# AdcUnit.net
KiCad netlist of a schematic drawn in Altium Designer
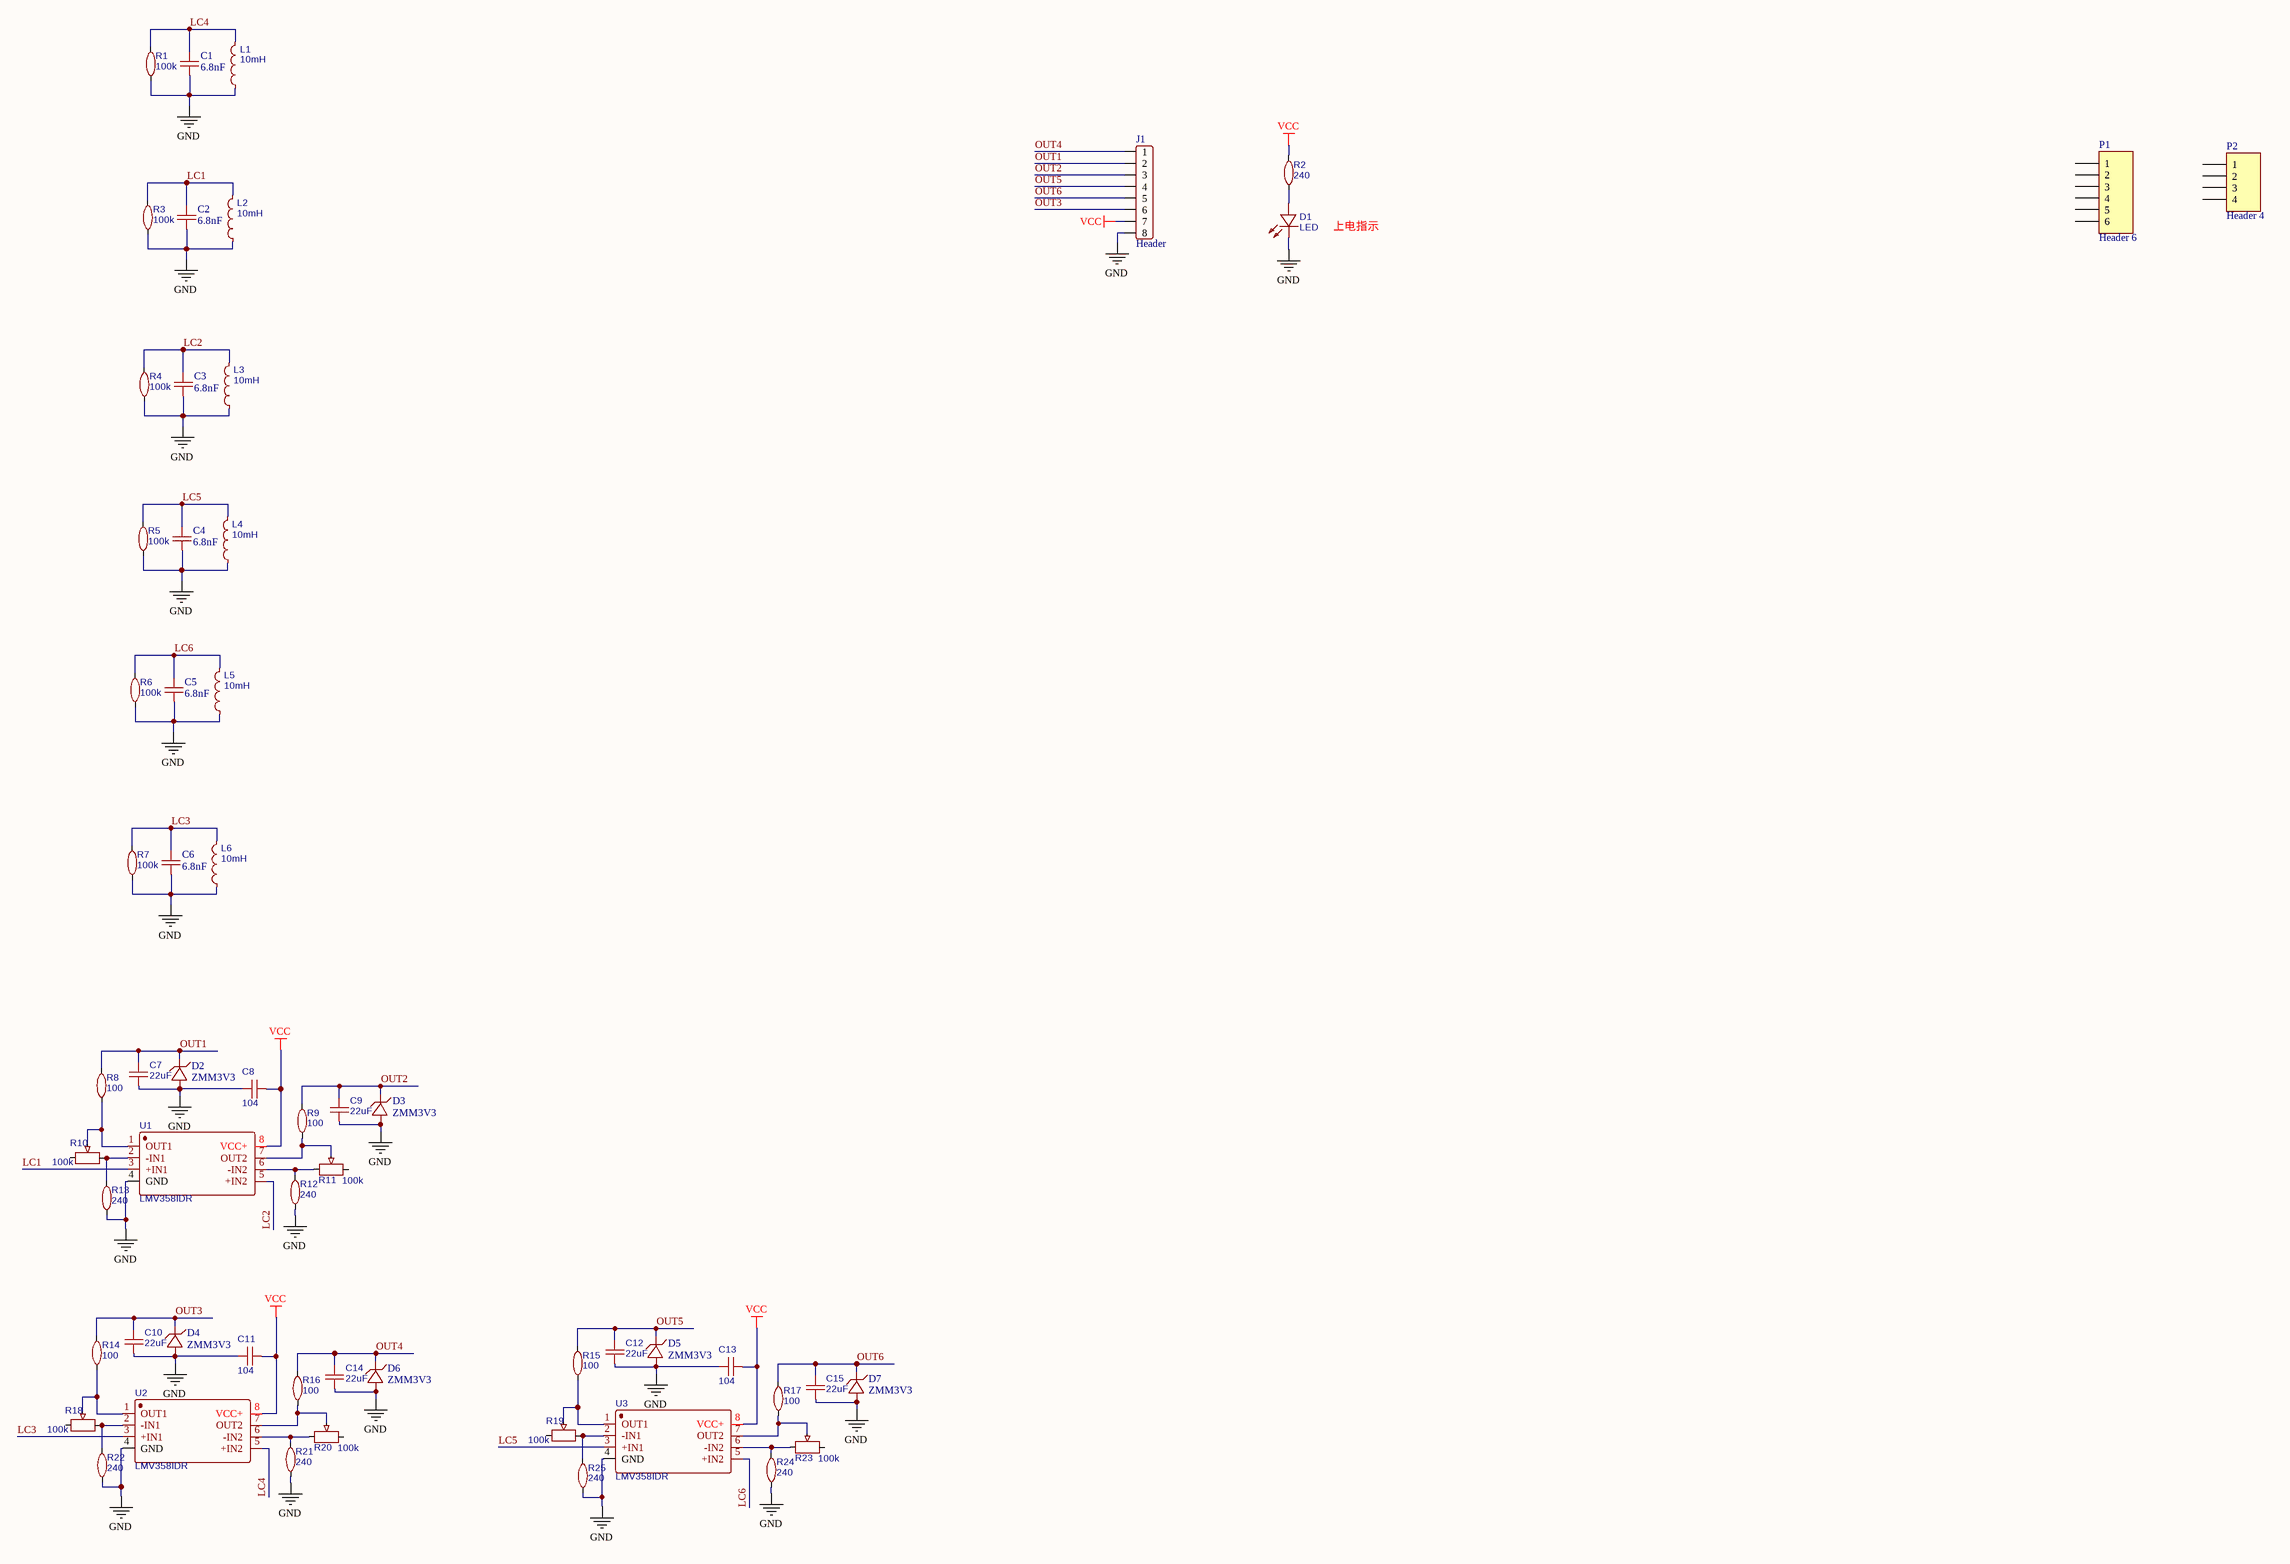
[diagram p0: AdcUnit.SchDoc]

(export (version "E")
  (design (tool "Eeschema 10.0.6"))
  (components
    (comp (ref "C1") (value "6.8nF") (footprint "CAP3") (libsource (lib "LTC_Library1") (part "CAP_聚苯电容")))
    (comp (ref "C2") (value "6.8nF") (footprint "CAP3") (libsource (lib "LTC_Library1") (part "CAP_聚苯电容")))
    (comp (ref "C3") (value "6.8nF") (footprint "CAP3") (libsource (lib "LTC_Library1") (part "CAP_聚苯电容")))
    (comp (ref "C4") (value "6.8nF") (footprint "CAP3") (libsource (lib "LTC_Library1") (part "CAP_聚苯电容")))
    (comp (ref "C5") (value "6.8nF") (footprint "CAP3") (libsource (lib "LTC_Library1") (part "CAP_聚苯电容")))
    (comp (ref "C6") (value "6.8nF") (footprint "CAP3") (libsource (lib "LTC_Library1") (part "CAP_聚苯电容")))
    (comp (ref "C7")
      (value "22uF")
      (footprint "CAP_0603")
      (fields
        (field (name "BOM_SUPPLIER PART") "C307348")
        (field (name "BOM_MANUFACTURER PART") "CL10B104KB8WPNC")
        (field (name "CONTRIBUTOR") "LCSC")
      )
      (libsource (lib "LTC_Library1") (part "CAP_0603"))
    )
    (comp (ref "C8")
      (value "104")
      (footprint "CAP_0603")
      (fields
        (field (name "BOM_SUPPLIER PART") "C307348")
        (field (name "BOM_MANUFACTURER PART") "CL10B104KB8WPNC")
        (field (name "CONTRIBUTOR") "LCSC")
      )
      (libsource (lib "LTC_Library1") (part "CAP_0603"))
    )
    (comp (ref "C9")
      (value "22uF")
      (footprint "CAP_0603")
      (fields
        (field (name "BOM_SUPPLIER PART") "C307348")
        (field (name "BOM_MANUFACTURER PART") "CL10B104KB8WPNC")
        (field (name "CONTRIBUTOR") "LCSC")
      )
      (libsource (lib "LTC_Library1") (part "CAP_0603"))
    )
    (comp (ref "C10")
      (value "22uF")
      (footprint "CAP_0603")
      (fields
        (field (name "BOM_SUPPLIER PART") "C307348")
        (field (name "BOM_MANUFACTURER PART") "CL10B104KB8WPNC")
        (field (name "CONTRIBUTOR") "LCSC")
      )
      (libsource (lib "LTC_Library1") (part "CAP_0603"))
    )
    (comp (ref "C11")
      (value "104")
      (footprint "CAP_0603")
      (fields
        (field (name "BOM_SUPPLIER PART") "C307348")
        (field (name "BOM_MANUFACTURER PART") "CL10B104KB8WPNC")
        (field (name "CONTRIBUTOR") "LCSC")
      )
      (libsource (lib "LTC_Library1") (part "CAP_0603"))
    )
    (comp (ref "C12")
      (value "22uF")
      (footprint "CAP_0603")
      (fields
        (field (name "BOM_SUPPLIER PART") "C307348")
        (field (name "BOM_MANUFACTURER PART") "CL10B104KB8WPNC")
        (field (name "CONTRIBUTOR") "LCSC")
      )
      (libsource (lib "LTC_Library1") (part "CAP_0603"))
    )
    (comp (ref "C13")
      (value "104")
      (footprint "CAP_0603")
      (fields
        (field (name "BOM_SUPPLIER PART") "C307348")
        (field (name "BOM_MANUFACTURER PART") "CL10B104KB8WPNC")
        (field (name "CONTRIBUTOR") "LCSC")
      )
      (libsource (lib "LTC_Library1") (part "CAP_0603"))
    )
    (comp (ref "C14")
      (value "22uF")
      (footprint "CAP_0603")
      (fields
        (field (name "BOM_SUPPLIER PART") "C307348")
        (field (name "BOM_MANUFACTURER PART") "CL10B104KB8WPNC")
        (field (name "CONTRIBUTOR") "LCSC")
      )
      (libsource (lib "LTC_Library1") (part "CAP_0603"))
    )
    (comp (ref "C15")
      (value "22uF")
      (footprint "CAP_0603")
      (fields
        (field (name "BOM_SUPPLIER PART") "C307348")
        (field (name "BOM_MANUFACTURER PART") "CL10B104KB8WPNC")
        (field (name "CONTRIBUTOR") "LCSC")
      )
      (libsource (lib "LTC_Library1") (part "CAP_0603"))
    )
    (comp (ref "D1")
      (value "LED")
      (footprint "LED_0603_B")
      (description "发光LED")
      (fields
        (field (name "BOM_MANUFACTURER PART") "D-G080508G1")
        (field (name "BOM_SUPPLIER PART") "C107402")
        (field (name "CONTRIBUTOR") "LCSC")
      )
      (libsource (lib "LTC_Library1") (part "LED_0603"))
    )
    (comp (ref "D2") (value "ZMM3V3") (footprint "LL34") (libsource (lib "LTC_Library1") (part "ZMM3V3")))
    (comp (ref "D3") (value "ZMM3V3") (footprint "LL34") (libsource (lib "LTC_Library1") (part "ZMM3V3")))
    (comp (ref "D4") (value "ZMM3V3") (footprint "LL34") (libsource (lib "LTC_Library1") (part "ZMM3V3")))
    (comp (ref "D5") (value "ZMM3V3") (footprint "LL34") (libsource (lib "LTC_Library1") (part "ZMM3V3")))
    (comp (ref "D6") (value "ZMM3V3") (footprint "LL34") (libsource (lib "LTC_Library1") (part "ZMM3V3")))
    (comp (ref "D7") (value "ZMM3V3") (footprint "LL34") (libsource (lib "LTC_Library1") (part "ZMM3V3")))
    (comp (ref "J1")
      (value "Header")
      (footprint "XH2.54-8P")
      (libsource (lib "LTC_Library1") (part "Header 2.54_8"))
    )
    (comp (ref "L1")
      (value "10mH")
      (footprint "Inductor_8x10")
      (fields
        (field (name "BOM_SUPPLIER PART") "C295130")
        (field (name "BOM_MANUFACTURER PART") "NLV25T-330J-EF")
        (field (name "CONTRIBUTOR") "LCSC")
      )
      (libsource (lib "LTC_Library1") (part "Inductor"))
    )
    (comp (ref "L2")
      (value "10mH")
      (footprint "Inductor_8x10")
      (fields
        (field (name "BOM_SUPPLIER PART") "C295130")
        (field (name "BOM_MANUFACTURER PART") "NLV25T-330J-EF")
        (field (name "CONTRIBUTOR") "LCSC")
      )
      (libsource (lib "LTC_Library1") (part "Inductor"))
    )
    (comp (ref "L3")
      (value "10mH")
      (footprint "Inductor_8x10")
      (fields
        (field (name "BOM_SUPPLIER PART") "C295130")
        (field (name "BOM_MANUFACTURER PART") "NLV25T-330J-EF")
        (field (name "CONTRIBUTOR") "LCSC")
      )
      (libsource (lib "LTC_Library1") (part "Inductor"))
    )
    (comp (ref "L4")
      (value "10mH")
      (footprint "Inductor_8x10")
      (fields
        (field (name "BOM_SUPPLIER PART") "C295130")
        (field (name "BOM_MANUFACTURER PART") "NLV25T-330J-EF")
        (field (name "CONTRIBUTOR") "LCSC")
      )
      (libsource (lib "LTC_Library1") (part "Inductor"))
    )
    (comp (ref "L5")
      (value "10mH")
      (footprint "Inductor_8x10")
      (fields
        (field (name "BOM_SUPPLIER PART") "C295130")
        (field (name "BOM_MANUFACTURER PART") "NLV25T-330J-EF")
        (field (name "CONTRIBUTOR") "LCSC")
      )
      (libsource (lib "LTC_Library1") (part "Inductor"))
    )
    (comp (ref "L6")
      (value "10mH")
      (footprint "Inductor_8x10")
      (fields
        (field (name "BOM_SUPPLIER PART") "C295130")
        (field (name "BOM_MANUFACTURER PART") "NLV25T-330J-EF")
        (field (name "CONTRIBUTOR") "LCSC")
      )
      (libsource (lib "LTC_Library1") (part "Inductor"))
    )
    (comp (ref "P1")
      (value "Header 6")
      (footprint "HDR-TH_6P_W")
      (description "Header, 6-Pin")
      (fields (field (name "PUBLISHER") "Altium Limited"))
      (libsource (lib "Miscellaneous Connectors") (part "Header 6"))
    )
    (comp (ref "P2")
      (value "Header 4")
      (footprint "XH2.54-4P")
      (description "Header, 4-Pin")
      (fields (field (name "PUBLISHER") "Altium Limited"))
      (libsource (lib "Miscellaneous Connectors") (part "Header 4"))
    )
    (comp (ref "R1")
      (value "100k")
      (footprint "RES_0603")
      (fields
        (field (name "BOM_MANUFACTURER PART") "RC0402JR-07100KL")
        (field (name "BOM_SUPPLIER PART") "C106234")
      )
      (libsource (lib "LTC_Library1") (part "RES_0603"))
    )
    (comp (ref "R2")
      (value "240")
      (footprint "RES_0603")
      (fields
        (field (name "BOM_MANUFACTURER PART") "RC0402JR-07100KL")
        (field (name "BOM_SUPPLIER PART") "C106234")
      )
      (libsource (lib "LTC_Library1") (part "RES_0603"))
    )
    (comp (ref "R3")
      (value "100k")
      (footprint "RES_0603")
      (fields
        (field (name "BOM_MANUFACTURER PART") "RC0402JR-07100KL")
        (field (name "BOM_SUPPLIER PART") "C106234")
      )
      (libsource (lib "LTC_Library1") (part "RES_0603"))
    )
    (comp (ref "R4")
      (value "100k")
      (footprint "RES_0603")
      (fields
        (field (name "BOM_MANUFACTURER PART") "RC0402JR-07100KL")
        (field (name "BOM_SUPPLIER PART") "C106234")
      )
      (libsource (lib "LTC_Library1") (part "RES_0603"))
    )
    (comp (ref "R5")
      (value "100k")
      (footprint "RES_0603")
      (fields
        (field (name "BOM_MANUFACTURER PART") "RC0402JR-07100KL")
        (field (name "BOM_SUPPLIER PART") "C106234")
      )
      (libsource (lib "LTC_Library1") (part "RES_0603"))
    )
    (comp (ref "R6")
      (value "100k")
      (footprint "RES_0603")
      (fields
        (field (name "BOM_MANUFACTURER PART") "RC0402JR-07100KL")
        (field (name "BOM_SUPPLIER PART") "C106234")
      )
      (libsource (lib "LTC_Library1") (part "RES_0603"))
    )
    (comp (ref "R7")
      (value "100k")
      (footprint "RES_0603")
      (fields
        (field (name "BOM_MANUFACTURER PART") "RC0402JR-07100KL")
        (field (name "BOM_SUPPLIER PART") "C106234")
      )
      (libsource (lib "LTC_Library1") (part "RES_0603"))
    )
    (comp (ref "R8")
      (value "100")
      (footprint "RES_0603")
      (fields
        (field (name "BOM_MANUFACTURER PART") "RC0402JR-07100KL")
        (field (name "BOM_SUPPLIER PART") "C106234")
      )
      (libsource (lib "LTC_Library1") (part "RES_0603"))
    )
    (comp (ref "R9")
      (value "100")
      (footprint "RES_0603")
      (fields
        (field (name "BOM_MANUFACTURER PART") "RC0402JR-07100KL")
        (field (name "BOM_SUPPLIER PART") "C106234")
      )
      (libsource (lib "LTC_Library1") (part "RES_0603"))
    )
    (comp (ref "R10")
      (value "100k")
      (footprint "RES_POT-3296W")
      (description "可调电阻3296W")
      (fields
        (field (name "BOM_SUPPLIER PART") "C118963")
        (field (name "BOM_MANUFACTURER PART") "3296W-1-104")
        (field (name "CONTRIBUTOR") "LCSC")
      )
      (libsource (lib "LTC_Library1") (part "RES_POT-3296W"))
    )
    (comp (ref "R11")
      (value "100k")
      (footprint "RES_POT-3296W")
      (description "可调电阻3296W")
      (fields
        (field (name "BOM_SUPPLIER PART") "C118963")
        (field (name "BOM_MANUFACTURER PART") "3296W-1-104")
        (field (name "CONTRIBUTOR") "LCSC")
      )
      (libsource (lib "LTC_Library1") (part "RES_POT-3296W"))
    )
    (comp (ref "R12")
      (value "240")
      (footprint "RES_0603")
      (fields
        (field (name "BOM_MANUFACTURER PART") "RC0402JR-07100KL")
        (field (name "BOM_SUPPLIER PART") "C106234")
      )
      (libsource (lib "LTC_Library1") (part "RES_0603"))
    )
    (comp (ref "R13")
      (value "240")
      (footprint "RES_0603")
      (fields
        (field (name "BOM_MANUFACTURER PART") "RC0402JR-07100KL")
        (field (name "BOM_SUPPLIER PART") "C106234")
      )
      (libsource (lib "LTC_Library1") (part "RES_0603"))
    )
    (comp (ref "R14")
      (value "100")
      (footprint "RES_0603")
      (fields
        (field (name "BOM_MANUFACTURER PART") "RC0402JR-07100KL")
        (field (name "BOM_SUPPLIER PART") "C106234")
      )
      (libsource (lib "LTC_Library1") (part "RES_0603"))
    )
    (comp (ref "R15")
      (value "100")
      (footprint "RES_0603")
      (fields
        (field (name "BOM_MANUFACTURER PART") "RC0402JR-07100KL")
        (field (name "BOM_SUPPLIER PART") "C106234")
      )
      (libsource (lib "LTC_Library1") (part "RES_0603"))
    )
    (comp (ref "R16")
      (value "100")
      (footprint "RES_0603")
      (fields
        (field (name "BOM_MANUFACTURER PART") "RC0402JR-07100KL")
        (field (name "BOM_SUPPLIER PART") "C106234")
      )
      (libsource (lib "LTC_Library1") (part "RES_0603"))
    )
    (comp (ref "R17")
      (value "100")
      (footprint "RES_0603")
      (fields
        (field (name "BOM_MANUFACTURER PART") "RC0402JR-07100KL")
        (field (name "BOM_SUPPLIER PART") "C106234")
      )
      (libsource (lib "LTC_Library1") (part "RES_0603"))
    )
    (comp (ref "R18")
      (value "100k")
      (footprint "RES_POT-3296W")
      (description "可调电阻3296W")
      (fields
        (field (name "BOM_SUPPLIER PART") "C118963")
        (field (name "BOM_MANUFACTURER PART") "3296W-1-104")
        (field (name "CONTRIBUTOR") "LCSC")
      )
      (libsource (lib "LTC_Library1") (part "RES_POT-3296W"))
    )
    (comp (ref "R19")
      (value "100k")
      (footprint "RES_POT-3296W")
      (description "可调电阻3296W")
      (fields
        (field (name "BOM_SUPPLIER PART") "C118963")
        (field (name "BOM_MANUFACTURER PART") "3296W-1-104")
        (field (name "CONTRIBUTOR") "LCSC")
      )
      (libsource (lib "LTC_Library1") (part "RES_POT-3296W"))
    )
    (comp (ref "R20")
      (value "100k")
      (footprint "RES_POT-3296W")
      (description "可调电阻3296W")
      (fields
        (field (name "BOM_SUPPLIER PART") "C118963")
        (field (name "BOM_MANUFACTURER PART") "3296W-1-104")
        (field (name "CONTRIBUTOR") "LCSC")
      )
      (libsource (lib "LTC_Library1") (part "RES_POT-3296W"))
    )
    (comp (ref "R21")
      (value "240")
      (footprint "RES_0603")
      (fields
        (field (name "BOM_MANUFACTURER PART") "RC0402JR-07100KL")
        (field (name "BOM_SUPPLIER PART") "C106234")
      )
      (libsource (lib "LTC_Library1") (part "RES_0603"))
    )
    (comp (ref "R22")
      (value "240")
      (footprint "RES_0603")
      (fields
        (field (name "BOM_MANUFACTURER PART") "RC0402JR-07100KL")
        (field (name "BOM_SUPPLIER PART") "C106234")
      )
      (libsource (lib "LTC_Library1") (part "RES_0603"))
    )
    (comp (ref "R23")
      (value "100k")
      (footprint "RES_POT-3296W")
      (description "可调电阻3296W")
      (fields
        (field (name "BOM_SUPPLIER PART") "C118963")
        (field (name "BOM_MANUFACTURER PART") "3296W-1-104")
        (field (name "CONTRIBUTOR") "LCSC")
      )
      (libsource (lib "LTC_Library1") (part "RES_POT-3296W"))
    )
    (comp (ref "R24")
      (value "240")
      (footprint "RES_0603")
      (fields
        (field (name "BOM_MANUFACTURER PART") "RC0402JR-07100KL")
        (field (name "BOM_SUPPLIER PART") "C106234")
      )
      (libsource (lib "LTC_Library1") (part "RES_0603"))
    )
    (comp (ref "R25")
      (value "240")
      (footprint "RES_0603")
      (fields
        (field (name "BOM_MANUFACTURER PART") "RC0402JR-07100KL")
        (field (name "BOM_SUPPLIER PART") "C106234")
      )
      (libsource (lib "LTC_Library1") (part "RES_0603"))
    )
    (comp (ref "U1")
      (value "LMV358IDR")
      (footprint "SOIC-8_150MIL")
      (fields (field (name "BOM_SUPPLIER PART") "C63813"))
      (libsource (lib "LTC_Library1") (part "LMV358IDR"))
    )
    (comp (ref "U2")
      (value "LMV358IDR")
      (footprint "SOIC-8_150MIL")
      (fields (field (name "BOM_SUPPLIER PART") "C63813"))
      (libsource (lib "LTC_Library1") (part "LMV358IDR"))
    )
    (comp (ref "U3")
      (value "LMV358IDR")
      (footprint "SOIC-8_150MIL")
      (fields (field (name "BOM_SUPPLIER PART") "C63813"))
      (libsource (lib "LTC_Library1") (part "LMV358IDR"))
    )
  )
  (nets
    (net (code "1") (name "/LC1") (class "Default")
      (node (ref "C2") (pin "1") (pinfunction "1_1") (pintype "passive"))
      (node (ref "L2") (pin "2") (pinfunction "2_2") (pintype "passive"))
      (node (ref "R3") (pin "2") (pinfunction "2_2") (pintype "passive"))
      (node (ref "U1") (pin "3") (pinfunction "+IN1_3") (pintype "passive"))
    )
    (net (code "2") (name "/LC2") (class "Default")
      (node (ref "C3") (pin "1") (pinfunction "1_1") (pintype "passive"))
      (node (ref "L3") (pin "2") (pinfunction "2_2") (pintype "passive"))
      (node (ref "R4") (pin "2") (pinfunction "2_2") (pintype "passive"))
      (node (ref "U1") (pin "5") (pinfunction "+IN2_5") (pintype "passive"))
    )
    (net (code "3") (name "/LC3") (class "Default")
      (node (ref "C6") (pin "1") (pinfunction "1_1") (pintype "passive"))
      (node (ref "L6") (pin "2") (pinfunction "2_2") (pintype "passive"))
      (node (ref "R7") (pin "2") (pinfunction "2_2") (pintype "passive"))
      (node (ref "U2") (pin "3") (pinfunction "+IN1_3") (pintype "passive"))
    )
    (net (code "4") (name "/LC4") (class "Default")
      (node (ref "C1") (pin "1") (pinfunction "1_1") (pintype "passive"))
      (node (ref "L1") (pin "2") (pinfunction "2_2") (pintype "passive"))
      (node (ref "R1") (pin "2") (pinfunction "2_2") (pintype "passive"))
      (node (ref "U2") (pin "5") (pinfunction "+IN2_5") (pintype "passive"))
    )
    (net (code "5") (name "/LC5") (class "Default")
      (node (ref "C4") (pin "1") (pinfunction "1_1") (pintype "passive"))
      (node (ref "L4") (pin "2") (pinfunction "2_2") (pintype "passive"))
      (node (ref "R5") (pin "2") (pinfunction "2_2") (pintype "passive"))
      (node (ref "U3") (pin "3") (pinfunction "+IN1_3") (pintype "passive"))
    )
    (net (code "6") (name "/LC6") (class "Default")
      (node (ref "C5") (pin "1") (pinfunction "1_1") (pintype "passive"))
      (node (ref "L5") (pin "2") (pinfunction "2_2") (pintype "passive"))
      (node (ref "R6") (pin "2") (pinfunction "2_2") (pintype "passive"))
      (node (ref "U3") (pin "5") (pinfunction "+IN2_5") (pintype "passive"))
    )
    (net (code "7") (name "/OUT1") (class "Default")
      (node (ref "C7") (pin "1") (pinfunction "1_1") (pintype "passive"))
      (node (ref "D2") (pin "2") (pinfunction "C_2") (pintype "passive"))
      (node (ref "J1") (pin "2") (pinfunction "2_2") (pintype "passive"))
      (node (ref "R8") (pin "2") (pinfunction "2_2") (pintype "passive"))
    )
    (net (code "8") (name "/OUT2") (class "Default")
      (node (ref "C9") (pin "1") (pinfunction "1_1") (pintype "passive"))
      (node (ref "D3") (pin "2") (pinfunction "C_2") (pintype "passive"))
      (node (ref "J1") (pin "3") (pinfunction "3_3") (pintype "passive"))
      (node (ref "R9") (pin "2") (pinfunction "2_2") (pintype "passive"))
    )
    (net (code "9") (name "/OUT3") (class "Default")
      (node (ref "C10") (pin "1") (pinfunction "1_1") (pintype "passive"))
      (node (ref "D4") (pin "2") (pinfunction "C_2") (pintype "passive"))
      (node (ref "J1") (pin "6") (pinfunction "6_6") (pintype "passive"))
      (node (ref "R14") (pin "2") (pinfunction "2_2") (pintype "passive"))
    )
    (net (code "10") (name "/OUT4") (class "Default")
      (node (ref "C14") (pin "1") (pinfunction "1_1") (pintype "passive"))
      (node (ref "D6") (pin "2") (pinfunction "C_2") (pintype "passive"))
      (node (ref "J1") (pin "1") (pinfunction "1_1") (pintype "passive"))
      (node (ref "R16") (pin "2") (pinfunction "2_2") (pintype "passive"))
    )
    (net (code "11") (name "/OUT5") (class "Default")
      (node (ref "C12") (pin "1") (pinfunction "1_1") (pintype "passive"))
      (node (ref "D5") (pin "2") (pinfunction "C_2") (pintype "passive"))
      (node (ref "J1") (pin "4") (pinfunction "4_4") (pintype "passive"))
      (node (ref "R15") (pin "2") (pinfunction "2_2") (pintype "passive"))
    )
    (net (code "12") (name "/OUT6") (class "Default")
      (node (ref "C15") (pin "1") (pinfunction "1_1") (pintype "passive"))
      (node (ref "D7") (pin "2") (pinfunction "C_2") (pintype "passive"))
      (node (ref "J1") (pin "5") (pinfunction "5_5") (pintype "passive"))
      (node (ref "R17") (pin "2") (pinfunction "2_2") (pintype "passive"))
    )
    (net (code "13") (name "GND") (class "Default")
      (node (ref "C1") (pin "2") (pinfunction "2_2") (pintype "passive"))
      (node (ref "C10") (pin "2") (pinfunction "2_2") (pintype "passive"))
      (node (ref "C11") (pin "1") (pinfunction "1_1") (pintype "passive"))
      (node (ref "C12") (pin "2") (pinfunction "2_2") (pintype "passive"))
      (node (ref "C13") (pin "1") (pinfunction "1_1") (pintype "passive"))
      (node (ref "C14") (pin "2") (pinfunction "2_2") (pintype "passive"))
      (node (ref "C15") (pin "2") (pinfunction "2_2") (pintype "passive"))
      (node (ref "C2") (pin "2") (pinfunction "2_2") (pintype "passive"))
      (node (ref "C3") (pin "2") (pinfunction "2_2") (pintype "passive"))
      (node (ref "C4") (pin "2") (pinfunction "2_2") (pintype "passive"))
      (node (ref "C5") (pin "2") (pinfunction "2_2") (pintype "passive"))
      (node (ref "C6") (pin "2") (pinfunction "2_2") (pintype "passive"))
      (node (ref "C7") (pin "2") (pinfunction "2_2") (pintype "passive"))
      (node (ref "C8") (pin "1") (pinfunction "1_1") (pintype "passive"))
      (node (ref "C9") (pin "2") (pinfunction "2_2") (pintype "passive"))
      (node (ref "D1") (pin "C") (pinfunction "C_C") (pintype "passive"))
      (node (ref "D2") (pin "1") (pinfunction "A_1") (pintype "passive"))
      (node (ref "D3") (pin "1") (pinfunction "A_1") (pintype "passive"))
      (node (ref "D4") (pin "1") (pinfunction "A_1") (pintype "passive"))
      (node (ref "D5") (pin "1") (pinfunction "A_1") (pintype "passive"))
      (node (ref "D6") (pin "1") (pinfunction "A_1") (pintype "passive"))
      (node (ref "D7") (pin "1") (pinfunction "A_1") (pintype "passive"))
      (node (ref "J1") (pin "8") (pinfunction "8_8") (pintype "passive"))
      (node (ref "L1") (pin "1") (pinfunction "1_1") (pintype "passive"))
      (node (ref "L2") (pin "1") (pinfunction "1_1") (pintype "passive"))
      (node (ref "L3") (pin "1") (pinfunction "1_1") (pintype "passive"))
      (node (ref "L4") (pin "1") (pinfunction "1_1") (pintype "passive"))
      (node (ref "L5") (pin "1") (pinfunction "1_1") (pintype "passive"))
      (node (ref "L6") (pin "1") (pinfunction "1_1") (pintype "passive"))
      (node (ref "R1") (pin "1") (pinfunction "1_1") (pintype "passive"))
      (node (ref "R12") (pin "1") (pinfunction "1_1") (pintype "passive"))
      (node (ref "R13") (pin "1") (pinfunction "1_1") (pintype "passive"))
      (node (ref "R21") (pin "1") (pinfunction "1_1") (pintype "passive"))
      (node (ref "R22") (pin "1") (pinfunction "1_1") (pintype "passive"))
      (node (ref "R24") (pin "1") (pinfunction "1_1") (pintype "passive"))
      (node (ref "R25") (pin "1") (pinfunction "1_1") (pintype "passive"))
      (node (ref "R3") (pin "1") (pinfunction "1_1") (pintype "passive"))
      (node (ref "R4") (pin "1") (pinfunction "1_1") (pintype "passive"))
      (node (ref "R5") (pin "1") (pinfunction "1_1") (pintype "passive"))
      (node (ref "R6") (pin "1") (pinfunction "1_1") (pintype "passive"))
      (node (ref "R7") (pin "1") (pinfunction "1_1") (pintype "passive"))
      (node (ref "U1") (pin "4") (pinfunction "GND_4") (pintype "passive"))
      (node (ref "U2") (pin "4") (pinfunction "GND_4") (pintype "passive"))
      (node (ref "U3") (pin "4") (pinfunction "GND_4") (pintype "passive"))
    )
    (net (code "14") (name "Net-(D1-PadA)") (class "Default")
      (node (ref "D1") (pin "A") (pinfunction "A_A") (pintype "passive"))
      (node (ref "R2") (pin "1") (pinfunction "1_1") (pintype "passive"))
    )
    (net (code "15") (name "Net-(U1--IN1)") (class "Default")
      (node (ref "R10") (pin "3") (pinfunction "3_3") (pintype "passive"))
      (node (ref "R13") (pin "2") (pinfunction "2_2") (pintype "passive"))
      (node (ref "U1") (pin "2") (pinfunction "-IN1_2") (pintype "passive"))
    )
    (net (code "16") (name "Net-(U1--IN2)") (class "Default")
      (node (ref "R11") (pin "1") (pinfunction "1_1") (pintype "passive"))
      (node (ref "R12") (pin "2") (pinfunction "2_2") (pintype "passive"))
      (node (ref "U1") (pin "6") (pinfunction "-IN2_6") (pintype "passive"))
    )
    (net (code "17") (name "Net-(U1-OUT1)") (class "Default")
      (node (ref "R10") (pin "2") (pinfunction "2_2") (pintype "passive"))
      (node (ref "R8") (pin "1") (pinfunction "1_1") (pintype "passive"))
      (node (ref "U1") (pin "1") (pinfunction "OUT1_1") (pintype "passive"))
    )
    (net (code "18") (name "Net-(U1-OUT2)") (class "Default")
      (node (ref "R11") (pin "2") (pinfunction "2_2") (pintype "passive"))
      (node (ref "R9") (pin "1") (pinfunction "1_1") (pintype "passive"))
      (node (ref "U1") (pin "7") (pinfunction "OUT2_7") (pintype "passive"))
    )
    (net (code "19") (name "Net-(U2--IN1)") (class "Default")
      (node (ref "R18") (pin "3") (pinfunction "3_3") (pintype "passive"))
      (node (ref "R22") (pin "2") (pinfunction "2_2") (pintype "passive"))
      (node (ref "U2") (pin "2") (pinfunction "-IN1_2") (pintype "passive"))
    )
    (net (code "20") (name "Net-(U2--IN2)") (class "Default")
      (node (ref "R20") (pin "1") (pinfunction "1_1") (pintype "passive"))
      (node (ref "R21") (pin "2") (pinfunction "2_2") (pintype "passive"))
      (node (ref "U2") (pin "6") (pinfunction "-IN2_6") (pintype "passive"))
    )
    (net (code "21") (name "Net-(U2-OUT1)") (class "Default")
      (node (ref "R14") (pin "1") (pinfunction "1_1") (pintype "passive"))
      (node (ref "R18") (pin "2") (pinfunction "2_2") (pintype "passive"))
      (node (ref "U2") (pin "1") (pinfunction "OUT1_1") (pintype "passive"))
    )
    (net (code "22") (name "Net-(U2-OUT2)") (class "Default")
      (node (ref "R16") (pin "1") (pinfunction "1_1") (pintype "passive"))
      (node (ref "R20") (pin "2") (pinfunction "2_2") (pintype "passive"))
      (node (ref "U2") (pin "7") (pinfunction "OUT2_7") (pintype "passive"))
    )
    (net (code "23") (name "Net-(U3--IN1)") (class "Default")
      (node (ref "R19") (pin "3") (pinfunction "3_3") (pintype "passive"))
      (node (ref "R25") (pin "2") (pinfunction "2_2") (pintype "passive"))
      (node (ref "U3") (pin "2") (pinfunction "-IN1_2") (pintype "passive"))
    )
    (net (code "24") (name "Net-(U3--IN2)") (class "Default")
      (node (ref "R23") (pin "1") (pinfunction "1_1") (pintype "passive"))
      (node (ref "R24") (pin "2") (pinfunction "2_2") (pintype "passive"))
      (node (ref "U3") (pin "6") (pinfunction "-IN2_6") (pintype "passive"))
    )
    (net (code "25") (name "Net-(U3-OUT1)") (class "Default")
      (node (ref "R15") (pin "1") (pinfunction "1_1") (pintype "passive"))
      (node (ref "R19") (pin "2") (pinfunction "2_2") (pintype "passive"))
      (node (ref "U3") (pin "1") (pinfunction "OUT1_1") (pintype "passive"))
    )
    (net (code "26") (name "Net-(U3-OUT2)") (class "Default")
      (node (ref "R17") (pin "1") (pinfunction "1_1") (pintype "passive"))
      (node (ref "R23") (pin "2") (pinfunction "2_2") (pintype "passive"))
      (node (ref "U3") (pin "7") (pinfunction "OUT2_7") (pintype "passive"))
    )
    (net (code "27") (name "VCC") (class "Default")
      (node (ref "C11") (pin "2") (pinfunction "2_2") (pintype "passive"))
      (node (ref "C13") (pin "2") (pinfunction "2_2") (pintype "passive"))
      (node (ref "C8") (pin "2") (pinfunction "2_2") (pintype "passive"))
      (node (ref "J1") (pin "7") (pinfunction "7_7") (pintype "passive"))
      (node (ref "R2") (pin "2") (pinfunction "2_2") (pintype "passive"))
      (node (ref "U1") (pin "8") (pinfunction "VCC+_8") (pintype "passive"))
      (node (ref "U2") (pin "8") (pinfunction "VCC+_8") (pintype "passive"))
      (node (ref "U3") (pin "8") (pinfunction "VCC+_8") (pintype "passive"))
    )
    (net (code "28") (name "unconnected-(P1-Pad1)") (class "Default")
      (node (ref "P1") (pin "1") (pinfunction "1_1") (pintype "passive"))
    )
    (net (code "29") (name "unconnected-(P1-Pad2)") (class "Default")
      (node (ref "P1") (pin "2") (pinfunction "2_2") (pintype "passive"))
    )
    (net (code "30") (name "unconnected-(P1-Pad3)") (class "Default")
      (node (ref "P1") (pin "3") (pinfunction "3_3") (pintype "passive"))
    )
    (net (code "31") (name "unconnected-(P1-Pad4)") (class "Default")
      (node (ref "P1") (pin "4") (pinfunction "4_4") (pintype "passive"))
    )
    (net (code "32") (name "unconnected-(P1-Pad5)") (class "Default")
      (node (ref "P1") (pin "5") (pinfunction "5_5") (pintype "passive"))
    )
    (net (code "33") (name "unconnected-(P1-Pad6)") (class "Default")
      (node (ref "P1") (pin "6") (pinfunction "6_6") (pintype "passive"))
    )
    (net (code "34") (name "unconnected-(P2-Pad1)") (class "Default")
      (node (ref "P2") (pin "1") (pinfunction "1_1") (pintype "passive"))
    )
    (net (code "35") (name "unconnected-(P2-Pad2)") (class "Default")
      (node (ref "P2") (pin "2") (pinfunction "2_2") (pintype "passive"))
    )
    (net (code "36") (name "unconnected-(P2-Pad3)") (class "Default")
      (node (ref "P2") (pin "3") (pinfunction "3_3") (pintype "passive"))
    )
    (net (code "37") (name "unconnected-(P2-Pad4)") (class "Default")
      (node (ref "P2") (pin "4") (pinfunction "4_4") (pintype "passive"))
    )
    (net (code "38") (name "unconnected-(R10-Pad1)") (class "Default")
      (node (ref "R10") (pin "1") (pinfunction "1_1") (pintype "passive"))
    )
    (net (code "39") (name "unconnected-(R11-Pad3)") (class "Default")
      (node (ref "R11") (pin "3") (pinfunction "3_3") (pintype "passive"))
    )
    (net (code "40") (name "unconnected-(R18-Pad1)") (class "Default")
      (node (ref "R18") (pin "1") (pinfunction "1_1") (pintype "passive"))
    )
    (net (code "41") (name "unconnected-(R19-Pad1)") (class "Default")
      (node (ref "R19") (pin "1") (pinfunction "1_1") (pintype "passive"))
    )
    (net (code "42") (name "unconnected-(R20-Pad3)") (class "Default")
      (node (ref "R20") (pin "3") (pinfunction "3_3") (pintype "passive"))
    )
    (net (code "43") (name "unconnected-(R23-Pad3)") (class "Default")
      (node (ref "R23") (pin "3") (pinfunction "3_3") (pintype "passive"))
    )
  )
)
